# OwlRack.net
KiCad netlist of a schematic drawn in EAGLE
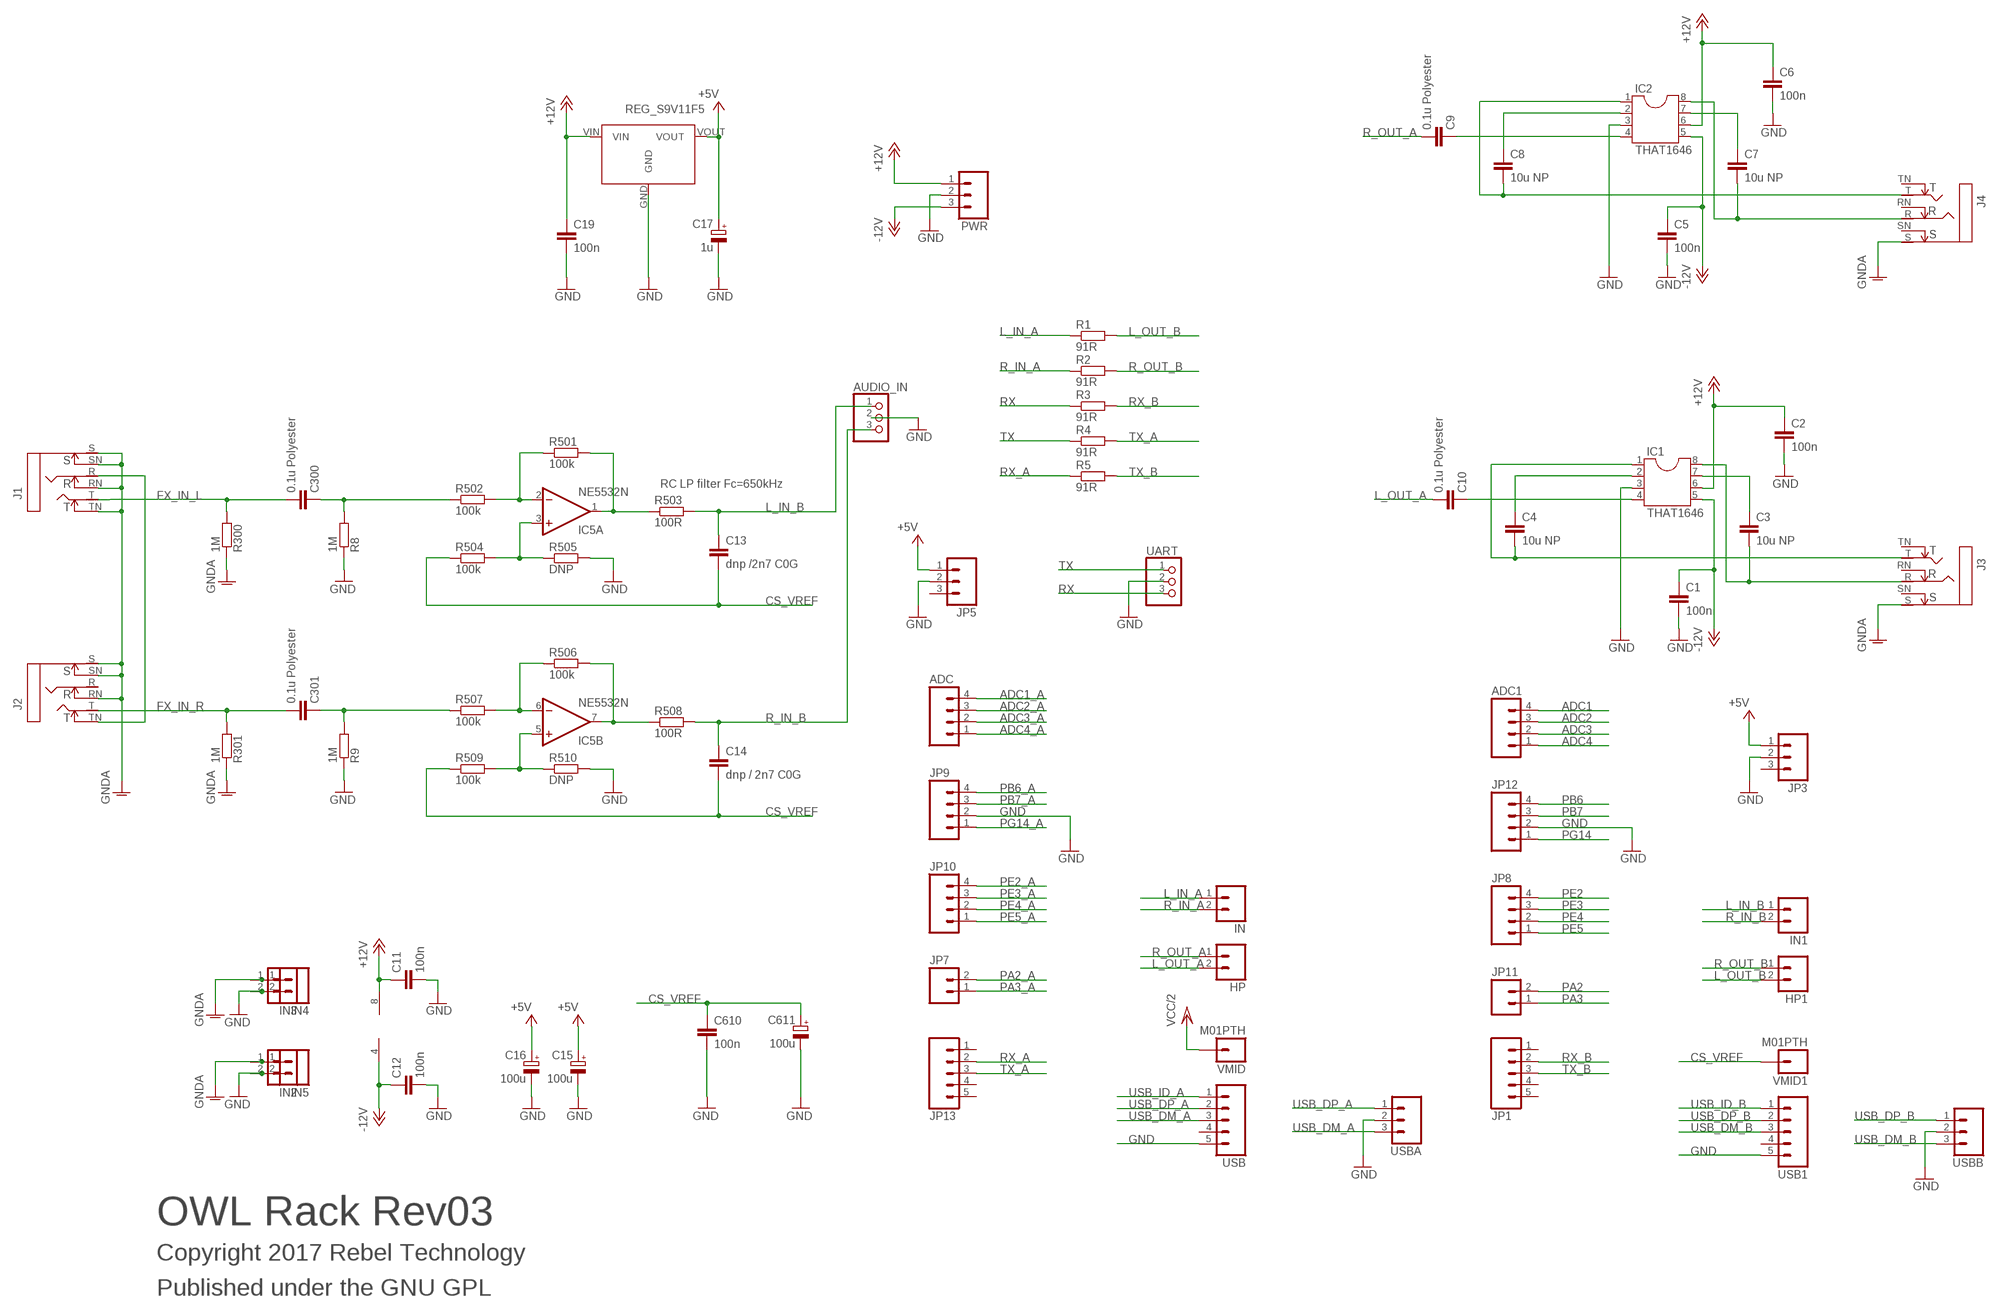
[diagram p0: schematic, sheet 1]

(export (version "E")
  (design (tool "Eeschema 10.0.6"))
  (components
    (comp (ref "ADC")
      (value "M04PTH")
      (footprint "eagle-import:1X04")
      (libsource (lib "eagle-import") (part "M04PTH"))
    )
    (comp (ref "ADC1")
      (value "M04PTH")
      (footprint "eagle-import:1X04")
      (libsource (lib "eagle-import") (part "M04PTH"))
    )
    (comp (ref "AUDIO_IN")
      (value "CON-JST-1X03PH-TH")
      (footprint "eagle-import:JST-B3B-PH-KL")
      (libsource (lib "eagle-import") (part "CON-JST-1X03PH-TH"))
    )
    (comp (ref "C1")
      (value "100n")
      (footprint "eagle-import:C050-025X075")
      (libsource (lib "eagle-import") (part "C-EU050-025X075"))
    )
    (comp (ref "C2")
      (value "100n")
      (footprint "eagle-import:C050-025X075")
      (libsource (lib "eagle-import") (part "C-EU050-025X075"))
    )
    (comp (ref "C3")
      (value "10u NP")
      (footprint "eagle-import:C050-025X075")
      (libsource (lib "eagle-import") (part "C-EU050-025X075"))
    )
    (comp (ref "C4")
      (value "10u NP")
      (footprint "eagle-import:C050-025X075")
      (libsource (lib "eagle-import") (part "C-EU050-025X075"))
    )
    (comp (ref "C5")
      (value "100n")
      (footprint "eagle-import:C050-025X075")
      (libsource (lib "eagle-import") (part "C-EU050-025X075"))
    )
    (comp (ref "C6")
      (value "100n")
      (footprint "eagle-import:C050-025X075")
      (libsource (lib "eagle-import") (part "C-EU050-025X075"))
    )
    (comp (ref "C7")
      (value "10u NP")
      (footprint "eagle-import:C050-025X075")
      (libsource (lib "eagle-import") (part "C-EU050-025X075"))
    )
    (comp (ref "C8")
      (value "10u NP")
      (footprint "eagle-import:C050-025X075")
      (libsource (lib "eagle-import") (part "C-EU050-025X075"))
    )
    (comp (ref "C9")
      (value "0.1u Polyester")
      (footprint "eagle-import:C5B3.5")
      (libsource (lib "eagle-import") (part "C5/3.5"))
    )
    (comp (ref "C10")
      (value "0.1u Polyester")
      (footprint "eagle-import:C5B3.5")
      (libsource (lib "eagle-import") (part "C5/3.5"))
    )
    (comp (ref "C11")
      (value "100n")
      (footprint "eagle-import:C050-025X075")
      (libsource (lib "eagle-import") (part "C-EU050-025X075"))
    )
    (comp (ref "C12")
      (value "100n")
      (footprint "eagle-import:C050-025X075")
      (libsource (lib "eagle-import") (part "C-EU050-025X075"))
    )
    (comp (ref "C13")
      (value "dnp /2n7 C0G")
      (footprint "eagle-import:C050-025X075")
      (libsource (lib "eagle-import") (part "C-EU050-025X075"))
    )
    (comp (ref "C14")
      (value "dnp / 2n7 C0G")
      (footprint "eagle-import:C050-025X075")
      (libsource (lib "eagle-import") (part "C-EU050-025X075"))
    )
    (comp (ref "C15")
      (value "100u")
      (footprint "eagle-import:E2,5-7")
      (libsource (lib "eagle-import") (part "CPOL-EUE2.5-7"))
    )
    (comp (ref "C16")
      (value "100u")
      (footprint "eagle-import:E2,5-7")
      (libsource (lib "eagle-import") (part "CPOL-EUE2.5-7"))
    )
    (comp (ref "C17")
      (value "1u")
      (footprint "eagle-import:E2,5-7")
      (libsource (lib "eagle-import") (part "CPOL-EUE2.5-7"))
    )
    (comp (ref "C19")
      (value "100n")
      (footprint "eagle-import:C050-025X075")
      (libsource (lib "eagle-import") (part "C-EU050-025X075"))
    )
    (comp (ref "C300")
      (value "0.1u Polyester")
      (footprint "eagle-import:C5B3.5")
      (libsource (lib "eagle-import") (part "C5/3.5"))
    )
    (comp (ref "C301")
      (value "0.1u Polyester")
      (footprint "eagle-import:C5B3.5")
      (libsource (lib "eagle-import") (part "C5/3.5"))
    )
    (comp (ref "C610")
      (value "100n")
      (footprint "eagle-import:C050-025X075")
      (libsource (lib "eagle-import") (part "C-EU050-025X075"))
    )
    (comp (ref "C611")
      (value "100u")
      (footprint "eagle-import:E2,5-7")
      (libsource (lib "eagle-import") (part "CPOL-EUE2.5-7"))
    )
    (comp (ref "HP")
      (value "M02PTH")
      (footprint "eagle-import:1X02")
      (libsource (lib "eagle-import") (part "M02PTH"))
    )
    (comp (ref "HP1")
      (value "M02PTH")
      (footprint "eagle-import:1X02")
      (libsource (lib "eagle-import") (part "M02PTH"))
    )
    (comp (ref "IC1")
      (value "THAT1646")
      (footprint "eagle-import:DIL08")
      (libsource (lib "eagle-import") (part "DIL8"))
    )
    (comp (ref "IC2")
      (value "THAT1646")
      (footprint "eagle-import:DIL08")
      (libsource (lib "eagle-import") (part "DIL8"))
    )
    (comp (ref "IC3")
      (value "REG_S9V11F5")
      (footprint "eagle-import:REG_S9V11F5")
      (libsource (lib "eagle-import") (part "REG_S9V11F5"))
    )
    (comp (ref "IC5")
      (value "NE5532N")
      (footprint "eagle-import:DIL08")
      (libsource (lib "eagle-import") (part "NE5532N"))
    )
    (comp (ref "IN")
      (value "M02PTH")
      (footprint "eagle-import:1X02")
      (libsource (lib "eagle-import") (part "M02PTH"))
    )
    (comp (ref "IN1")
      (value "M02PTH")
      (footprint "eagle-import:1X02")
      (libsource (lib "eagle-import") (part "M02PTH"))
    )
    (comp (ref "IN2")
      (value "M02PTH")
      (footprint "eagle-import:1X02")
      (libsource (lib "eagle-import") (part "M02PTH"))
    )
    (comp (ref "IN3")
      (value "M02PTH")
      (footprint "eagle-import:1X02")
      (libsource (lib "eagle-import") (part "M02PTH"))
    )
    (comp (ref "IN4")
      (value "M02PTH")
      (footprint "eagle-import:1X02")
      (libsource (lib "eagle-import") (part "M02PTH"))
    )
    (comp (ref "IN5")
      (value "M02PTH")
      (footprint "eagle-import:1X02")
      (libsource (lib "eagle-import") (part "M02PTH"))
    )
    (comp (ref "J1")
      (value "NEUTRIK_NRJ6HFSTD")
      (footprint "eagle-import:NRJ6HF")
      (libsource (lib "eagle-import") (part "NEUTRIK_NRJ6HFSTD"))
    )
    (comp (ref "J2")
      (value "NEUTRIK_NRJ6HFSTD")
      (footprint "eagle-import:NRJ6HF")
      (libsource (lib "eagle-import") (part "NEUTRIK_NRJ6HFSTD"))
    )
    (comp (ref "J3")
      (value "NEUTRIK_NRJ6HFSTD")
      (footprint "eagle-import:NRJ6HF")
      (libsource (lib "eagle-import") (part "NEUTRIK_NRJ6HFSTD"))
    )
    (comp (ref "J4")
      (value "NEUTRIK_NRJ6HFSTD")
      (footprint "eagle-import:NRJ6HF")
      (libsource (lib "eagle-import") (part "NEUTRIK_NRJ6HFSTD"))
    )
    (comp (ref "JP1")
      (value "M05PTH")
      (footprint "eagle-import:1X05")
      (libsource (lib "eagle-import") (part "M05PTH"))
    )
    (comp (ref "JP3")
      (value "M03PTH")
      (footprint "eagle-import:1X03")
      (libsource (lib "eagle-import") (part "M03PTH"))
    )
    (comp (ref "JP5")
      (value "M03PTH")
      (footprint "eagle-import:1X03")
      (libsource (lib "eagle-import") (part "M03PTH"))
    )
    (comp (ref "JP7")
      (value "M02PTH")
      (footprint "eagle-import:1X02")
      (libsource (lib "eagle-import") (part "M02PTH"))
    )
    (comp (ref "JP8")
      (value "M04PTH")
      (footprint "eagle-import:1X04")
      (libsource (lib "eagle-import") (part "M04PTH"))
    )
    (comp (ref "JP9")
      (value "M04PTH")
      (footprint "eagle-import:1X04")
      (libsource (lib "eagle-import") (part "M04PTH"))
    )
    (comp (ref "JP10")
      (value "M04PTH")
      (footprint "eagle-import:1X04")
      (libsource (lib "eagle-import") (part "M04PTH"))
    )
    (comp (ref "JP11")
      (value "M02PTH")
      (footprint "eagle-import:1X02")
      (libsource (lib "eagle-import") (part "M02PTH"))
    )
    (comp (ref "JP12")
      (value "M04PTH")
      (footprint "eagle-import:1X04")
      (libsource (lib "eagle-import") (part "M04PTH"))
    )
    (comp (ref "JP13")
      (value "M05PTH")
      (footprint "eagle-import:1X05")
      (libsource (lib "eagle-import") (part "M05PTH"))
    )
    (comp (ref "PWR")
      (value "M03PTH")
      (footprint "eagle-import:1X03")
      (libsource (lib "eagle-import") (part "M03PTH"))
    )
    (comp (ref "R1")
      (value "91R")
      (footprint "eagle-import:0204_7")
      (libsource (lib "eagle-import") (part "R-EU_0204/7"))
    )
    (comp (ref "R2")
      (value "91R")
      (footprint "eagle-import:0204_7")
      (libsource (lib "eagle-import") (part "R-EU_0204/7"))
    )
    (comp (ref "R3")
      (value "91R")
      (footprint "eagle-import:0204_7")
      (libsource (lib "eagle-import") (part "R-EU_0204/7"))
    )
    (comp (ref "R4")
      (value "91R")
      (footprint "eagle-import:0204_7")
      (libsource (lib "eagle-import") (part "R-EU_0204/7"))
    )
    (comp (ref "R5")
      (value "91R")
      (footprint "eagle-import:0204_7")
      (libsource (lib "eagle-import") (part "R-EU_0204/7"))
    )
    (comp (ref "R8")
      (value "1M")
      (footprint "eagle-import:0204_7")
      (libsource (lib "eagle-import") (part "R-EU_0204/7"))
    )
    (comp (ref "R9")
      (value "1M")
      (footprint "eagle-import:0204_7")
      (libsource (lib "eagle-import") (part "R-EU_0204/7"))
    )
    (comp (ref "R300")
      (value "1M")
      (footprint "eagle-import:0204_7")
      (libsource (lib "eagle-import") (part "R-EU_0204/7"))
    )
    (comp (ref "R301")
      (value "1M")
      (footprint "eagle-import:0204_7")
      (libsource (lib "eagle-import") (part "R-EU_0204/7"))
    )
    (comp (ref "R501")
      (value "100k")
      (footprint "eagle-import:0204_7")
      (libsource (lib "eagle-import") (part "R-EU_0204/7"))
    )
    (comp (ref "R502")
      (value "100k")
      (footprint "eagle-import:0204_7")
      (libsource (lib "eagle-import") (part "R-EU_0204/7"))
    )
    (comp (ref "R503")
      (value "100R")
      (footprint "eagle-import:0204_7")
      (libsource (lib "eagle-import") (part "R-EU_0204/7"))
    )
    (comp (ref "R504")
      (value "100k")
      (footprint "eagle-import:0204_7")
      (libsource (lib "eagle-import") (part "R-EU_0204/7"))
    )
    (comp (ref "R505")
      (value "DNP")
      (footprint "eagle-import:0204_7")
      (libsource (lib "eagle-import") (part "R-EU_0204/7"))
    )
    (comp (ref "R506")
      (value "100k")
      (footprint "eagle-import:0204_7")
      (libsource (lib "eagle-import") (part "R-EU_0204/7"))
    )
    (comp (ref "R507")
      (value "100k")
      (footprint "eagle-import:0204_7")
      (libsource (lib "eagle-import") (part "R-EU_0204/7"))
    )
    (comp (ref "R508")
      (value "100R")
      (footprint "eagle-import:0204_7")
      (libsource (lib "eagle-import") (part "R-EU_0204/7"))
    )
    (comp (ref "R509")
      (value "100k")
      (footprint "eagle-import:0204_7")
      (libsource (lib "eagle-import") (part "R-EU_0204/7"))
    )
    (comp (ref "R510")
      (value "DNP")
      (footprint "eagle-import:0204_7")
      (libsource (lib "eagle-import") (part "R-EU_0204/7"))
    )
    (comp (ref "UART")
      (value "CON-JST-1X03PH-TH")
      (footprint "eagle-import:JST-B3B-PH-KL")
      (libsource (lib "eagle-import") (part "CON-JST-1X03PH-TH"))
    )
    (comp (ref "USB")
      (value "M05PTH")
      (footprint "eagle-import:1X05")
      (libsource (lib "eagle-import") (part "M05PTH"))
    )
    (comp (ref "USB1")
      (value "M05PTH")
      (footprint "eagle-import:1X05")
      (libsource (lib "eagle-import") (part "M05PTH"))
    )
    (comp (ref "USBA")
      (value "M03PTH")
      (footprint "eagle-import:1X03")
      (libsource (lib "eagle-import") (part "M03PTH"))
    )
    (comp (ref "USBB")
      (value "M03PTH")
      (footprint "eagle-import:1X03")
      (libsource (lib "eagle-import") (part "M03PTH"))
    )
    (comp (ref "VMID")
      (value "M01PTH")
      (footprint "eagle-import:1X01")
      (libsource (lib "eagle-import") (part "M01PTH"))
    )
    (comp (ref "VMID1")
      (value "M01PTH")
      (footprint "eagle-import:1X01")
      (libsource (lib "eagle-import") (part "M01PTH"))
    )
  )
  (nets
    (net (code "1") (name "+5V") (class "Default")
      (node (ref "C15") (pin "+") (pinfunction "+_+") (pintype "passive"))
      (node (ref "C16") (pin "+") (pinfunction "+_+") (pintype "passive"))
      (node (ref "C17") (pin "+") (pinfunction "+_+") (pintype "passive"))
      (node (ref "IC3") (pin "VOUT") (pinfunction "VOUT_VOUT") (pintype "output"))
      (node (ref "JP3") (pin "1") (pinfunction "1_1") (pintype "passive"))
      (node (ref "JP5") (pin "1") (pinfunction "1_1") (pintype "passive"))
    )
    (net (code "2") (name "+12V") (class "Default")
      (node (ref "C11") (pin "1") (pinfunction "1_1") (pintype "passive"))
      (node (ref "C19") (pin "1") (pinfunction "1_1") (pintype "passive"))
      (node (ref "C2") (pin "1") (pinfunction "1_1") (pintype "passive"))
      (node (ref "C6") (pin "1") (pinfunction "1_1") (pintype "passive"))
      (node (ref "IC1") (pin "6") (pinfunction "6_6") (pintype "passive"))
      (node (ref "IC2") (pin "6") (pinfunction "6_6") (pintype "passive"))
      (node (ref "IC3") (pin "VIN") (pinfunction "VIN_VIN") (pintype "input"))
      (node (ref "IC5") (pin "8") (pinfunction "V+_8") (pintype "power_in"))
      (node (ref "PWR") (pin "1") (pinfunction "1_1") (pintype "passive"))
    )
    (net (code "3") (name "-12V") (class "Default")
      (node (ref "C1") (pin "1") (pinfunction "1_1") (pintype "passive"))
      (node (ref "C12") (pin "1") (pinfunction "1_1") (pintype "passive"))
      (node (ref "C5") (pin "1") (pinfunction "1_1") (pintype "passive"))
      (node (ref "IC1") (pin "5") (pinfunction "5_5") (pintype "passive"))
      (node (ref "IC2") (pin "5") (pinfunction "5_5") (pintype "passive"))
      (node (ref "IC5") (pin "4") (pinfunction "V-_4") (pintype "power_in"))
      (node (ref "PWR") (pin "3") (pinfunction "3_3") (pintype "passive"))
    )
    (net (code "4") (name "/ADC1") (class "Default")
      (node (ref "ADC1") (pin "4") (pinfunction "4_4") (pintype "passive"))
    )
    (net (code "5") (name "/ADC1_A") (class "Default")
      (node (ref "ADC") (pin "4") (pinfunction "4_4") (pintype "passive"))
    )
    (net (code "6") (name "/ADC2") (class "Default")
      (node (ref "ADC1") (pin "3") (pinfunction "3_3") (pintype "passive"))
    )
    (net (code "7") (name "/ADC2_A") (class "Default")
      (node (ref "ADC") (pin "3") (pinfunction "3_3") (pintype "passive"))
    )
    (net (code "8") (name "/ADC3") (class "Default")
      (node (ref "ADC1") (pin "2") (pinfunction "2_2") (pintype "passive"))
    )
    (net (code "9") (name "/ADC3_A") (class "Default")
      (node (ref "ADC") (pin "2") (pinfunction "2_2") (pintype "passive"))
    )
    (net (code "10") (name "/ADC4") (class "Default")
      (node (ref "ADC1") (pin "1") (pinfunction "1_1") (pintype "passive"))
    )
    (net (code "11") (name "/ADC4_A") (class "Default")
      (node (ref "ADC") (pin "1") (pinfunction "1_1") (pintype "passive"))
    )
    (net (code "12") (name "/CS_VREF") (class "Default")
      (node (ref "C13") (pin "2") (pinfunction "2_2") (pintype "passive"))
      (node (ref "C14") (pin "2") (pinfunction "2_2") (pintype "passive"))
      (node (ref "C610") (pin "1") (pinfunction "1_1") (pintype "passive"))
      (node (ref "C611") (pin "+") (pinfunction "+_+") (pintype "passive"))
      (node (ref "R504") (pin "1") (pinfunction "1_1") (pintype "passive"))
      (node (ref "R509") (pin "1") (pinfunction "1_1") (pintype "passive"))
      (node (ref "VMID1") (pin "1") (pinfunction "1_1") (pintype "passive"))
    )
    (net (code "13") (name "/FX_IN_L") (class "Default")
      (node (ref "C300") (pin "2") (pinfunction "2_2") (pintype "passive"))
      (node (ref "J1") (pin "T") (pinfunction "T_T") (pintype "passive"))
      (node (ref "R300") (pin "2") (pinfunction "2_2") (pintype "passive"))
    )
    (net (code "14") (name "/FX_IN_R") (class "Default")
      (node (ref "C301") (pin "2") (pinfunction "2_2") (pintype "passive"))
      (node (ref "J2") (pin "T") (pinfunction "T_T") (pintype "passive"))
      (node (ref "R301") (pin "2") (pinfunction "2_2") (pintype "passive"))
    )
    (net (code "15") (name "/L_IN_A") (class "Default")
      (node (ref "IN") (pin "1") (pinfunction "1_1") (pintype "passive"))
      (node (ref "R1") (pin "1") (pinfunction "1_1") (pintype "passive"))
    )
    (net (code "16") (name "/L_IN_B") (class "Default")
      (node (ref "AUDIO_IN") (pin "1") (pinfunction "1_1") (pintype "passive"))
      (node (ref "C13") (pin "1") (pinfunction "1_1") (pintype "passive"))
      (node (ref "IN1") (pin "1") (pinfunction "1_1") (pintype "passive"))
      (node (ref "R503") (pin "2") (pinfunction "2_2") (pintype "passive"))
    )
    (net (code "17") (name "/L_OUT_A") (class "Default")
      (node (ref "C10") (pin "2") (pinfunction "2_2") (pintype "passive"))
      (node (ref "HP") (pin "2") (pinfunction "2_2") (pintype "passive"))
    )
    (net (code "18") (name "/L_OUT_B") (class "Default")
      (node (ref "HP1") (pin "2") (pinfunction "2_2") (pintype "passive"))
      (node (ref "R1") (pin "2") (pinfunction "2_2") (pintype "passive"))
    )
    (net (code "19") (name "/PA2") (class "Default")
      (node (ref "JP11") (pin "2") (pinfunction "2_2") (pintype "passive"))
    )
    (net (code "20") (name "/PA2_A") (class "Default")
      (node (ref "JP7") (pin "2") (pinfunction "2_2") (pintype "passive"))
    )
    (net (code "21") (name "/PA3") (class "Default")
      (node (ref "JP11") (pin "1") (pinfunction "1_1") (pintype "passive"))
    )
    (net (code "22") (name "/PA3_A") (class "Default")
      (node (ref "JP7") (pin "1") (pinfunction "1_1") (pintype "passive"))
    )
    (net (code "23") (name "/PB6") (class "Default")
      (node (ref "JP12") (pin "4") (pinfunction "4_4") (pintype "passive"))
    )
    (net (code "24") (name "/PB6_A") (class "Default")
      (node (ref "JP9") (pin "4") (pinfunction "4_4") (pintype "passive"))
    )
    (net (code "25") (name "/PB7") (class "Default")
      (node (ref "JP12") (pin "3") (pinfunction "3_3") (pintype "passive"))
    )
    (net (code "26") (name "/PB7_A") (class "Default")
      (node (ref "JP9") (pin "3") (pinfunction "3_3") (pintype "passive"))
    )
    (net (code "27") (name "/PE2") (class "Default")
      (node (ref "JP8") (pin "4") (pinfunction "4_4") (pintype "passive"))
    )
    (net (code "28") (name "/PE2_A") (class "Default")
      (node (ref "JP10") (pin "4") (pinfunction "4_4") (pintype "passive"))
    )
    (net (code "29") (name "/PE3") (class "Default")
      (node (ref "JP8") (pin "3") (pinfunction "3_3") (pintype "passive"))
    )
    (net (code "30") (name "/PE3_A") (class "Default")
      (node (ref "JP10") (pin "3") (pinfunction "3_3") (pintype "passive"))
    )
    (net (code "31") (name "/PE4") (class "Default")
      (node (ref "JP8") (pin "2") (pinfunction "2_2") (pintype "passive"))
    )
    (net (code "32") (name "/PE4_A") (class "Default")
      (node (ref "JP10") (pin "2") (pinfunction "2_2") (pintype "passive"))
    )
    (net (code "33") (name "/PE5") (class "Default")
      (node (ref "JP8") (pin "1") (pinfunction "1_1") (pintype "passive"))
    )
    (net (code "34") (name "/PE5_A") (class "Default")
      (node (ref "JP10") (pin "1") (pinfunction "1_1") (pintype "passive"))
    )
    (net (code "35") (name "/PG14") (class "Default")
      (node (ref "JP12") (pin "1") (pinfunction "1_1") (pintype "passive"))
    )
    (net (code "36") (name "/PG14_A") (class "Default")
      (node (ref "JP9") (pin "1") (pinfunction "1_1") (pintype "passive"))
    )
    (net (code "37") (name "/RX") (class "Default")
      (node (ref "R3") (pin "1") (pinfunction "1_1") (pintype "passive"))
      (node (ref "UART") (pin "3") (pinfunction "3_3") (pintype "passive"))
    )
    (net (code "38") (name "/RX_A") (class "Default")
      (node (ref "JP13") (pin "2") (pinfunction "2_2") (pintype "passive"))
      (node (ref "R5") (pin "1") (pinfunction "1_1") (pintype "passive"))
    )
    (net (code "39") (name "/RX_B") (class "Default")
      (node (ref "JP1") (pin "2") (pinfunction "2_2") (pintype "passive"))
      (node (ref "R3") (pin "2") (pinfunction "2_2") (pintype "passive"))
    )
    (net (code "40") (name "/R_IN_A") (class "Default")
      (node (ref "IN") (pin "2") (pinfunction "2_2") (pintype "passive"))
      (node (ref "R2") (pin "1") (pinfunction "1_1") (pintype "passive"))
    )
    (net (code "41") (name "/R_IN_B") (class "Default")
      (node (ref "AUDIO_IN") (pin "3") (pinfunction "3_3") (pintype "passive"))
      (node (ref "C14") (pin "1") (pinfunction "1_1") (pintype "passive"))
      (node (ref "IN1") (pin "2") (pinfunction "2_2") (pintype "passive"))
      (node (ref "R508") (pin "2") (pinfunction "2_2") (pintype "passive"))
    )
    (net (code "42") (name "/R_OUT_A") (class "Default")
      (node (ref "C9") (pin "2") (pinfunction "2_2") (pintype "passive"))
      (node (ref "HP") (pin "1") (pinfunction "1_1") (pintype "passive"))
    )
    (net (code "43") (name "/R_OUT_B") (class "Default")
      (node (ref "HP1") (pin "1") (pinfunction "1_1") (pintype "passive"))
      (node (ref "R2") (pin "2") (pinfunction "2_2") (pintype "passive"))
    )
    (net (code "44") (name "/TX") (class "Default")
      (node (ref "R4") (pin "1") (pinfunction "1_1") (pintype "passive"))
      (node (ref "UART") (pin "1") (pinfunction "1_1") (pintype "passive"))
    )
    (net (code "45") (name "/TX_A") (class "Default")
      (node (ref "JP13") (pin "3") (pinfunction "3_3") (pintype "passive"))
      (node (ref "R4") (pin "2") (pinfunction "2_2") (pintype "passive"))
    )
    (net (code "46") (name "/TX_B") (class "Default")
      (node (ref "JP1") (pin "3") (pinfunction "3_3") (pintype "passive"))
      (node (ref "R5") (pin "2") (pinfunction "2_2") (pintype "passive"))
    )
    (net (code "47") (name "/USB_DM_A") (class "Default")
      (node (ref "USB") (pin "3") (pinfunction "3_3") (pintype "passive"))
      (node (ref "USBA") (pin "3") (pinfunction "3_3") (pintype "passive"))
    )
    (net (code "48") (name "/USB_DM_B") (class "Default")
      (node (ref "USB1") (pin "3") (pinfunction "3_3") (pintype "passive"))
      (node (ref "USBB") (pin "3") (pinfunction "3_3") (pintype "passive"))
    )
    (net (code "49") (name "/USB_DP_A") (class "Default")
      (node (ref "USB") (pin "2") (pinfunction "2_2") (pintype "passive"))
      (node (ref "USBA") (pin "1") (pinfunction "1_1") (pintype "passive"))
    )
    (net (code "50") (name "/USB_DP_B") (class "Default")
      (node (ref "USB1") (pin "2") (pinfunction "2_2") (pintype "passive"))
      (node (ref "USBB") (pin "1") (pinfunction "1_1") (pintype "passive"))
    )
    (net (code "51") (name "/USB_ID_A") (class "Default")
      (node (ref "USB") (pin "1") (pinfunction "1_1") (pintype "passive"))
    )
    (net (code "52") (name "/USB_ID_B") (class "Default")
      (node (ref "USB1") (pin "1") (pinfunction "1_1") (pintype "passive"))
    )
    (net (code "53") (name "GND") (class "Default")
      (node (ref "AUDIO_IN") (pin "2") (pinfunction "2_2") (pintype "passive"))
      (node (ref "C1") (pin "2") (pinfunction "2_2") (pintype "passive"))
      (node (ref "C11") (pin "2") (pinfunction "2_2") (pintype "passive"))
      (node (ref "C12") (pin "2") (pinfunction "2_2") (pintype "passive"))
      (node (ref "C15") (pin "-") (pinfunction "-_-") (pintype "passive"))
      (node (ref "C16") (pin "-") (pinfunction "-_-") (pintype "passive"))
      (node (ref "C17") (pin "-") (pinfunction "-_-") (pintype "passive"))
      (node (ref "C19") (pin "2") (pinfunction "2_2") (pintype "passive"))
      (node (ref "C2") (pin "2") (pinfunction "2_2") (pintype "passive"))
      (node (ref "C5") (pin "2") (pinfunction "2_2") (pintype "passive"))
      (node (ref "C6") (pin "2") (pinfunction "2_2") (pintype "passive"))
      (node (ref "C610") (pin "2") (pinfunction "2_2") (pintype "passive"))
      (node (ref "C611") (pin "-") (pinfunction "-_-") (pintype "passive"))
      (node (ref "IC1") (pin "3") (pinfunction "3_3") (pintype "passive"))
      (node (ref "IC2") (pin "3") (pinfunction "3_3") (pintype "passive"))
      (node (ref "IC3") (pin "GND") (pinfunction "GND_GND") (pintype "power_in"))
      (node (ref "IN2") (pin "2") (pinfunction "2_2") (pintype "passive"))
      (node (ref "IN3") (pin "2") (pinfunction "2_2") (pintype "passive"))
      (node (ref "IN4") (pin "2") (pinfunction "2_2") (pintype "passive"))
      (node (ref "IN5") (pin "2") (pinfunction "2_2") (pintype "passive"))
      (node (ref "JP12") (pin "2") (pinfunction "2_2") (pintype "passive"))
      (node (ref "JP3") (pin "2") (pinfunction "2_2") (pintype "passive"))
      (node (ref "JP5") (pin "2") (pinfunction "2_2") (pintype "passive"))
      (node (ref "JP9") (pin "2") (pinfunction "2_2") (pintype "passive"))
      (node (ref "PWR") (pin "2") (pinfunction "2_2") (pintype "passive"))
      (node (ref "R505") (pin "2") (pinfunction "2_2") (pintype "passive"))
      (node (ref "R510") (pin "2") (pinfunction "2_2") (pintype "passive"))
      (node (ref "R8") (pin "1") (pinfunction "1_1") (pintype "passive"))
      (node (ref "R9") (pin "1") (pinfunction "1_1") (pintype "passive"))
      (node (ref "UART") (pin "2") (pinfunction "2_2") (pintype "passive"))
      (node (ref "USB") (pin "5") (pinfunction "5_5") (pintype "passive"))
      (node (ref "USB1") (pin "5") (pinfunction "5_5") (pintype "passive"))
      (node (ref "USBA") (pin "2") (pinfunction "2_2") (pintype "passive"))
      (node (ref "USBB") (pin "2") (pinfunction "2_2") (pintype "passive"))
    )
    (net (code "54") (name "GNDA") (class "Default")
      (node (ref "IN2") (pin "1") (pinfunction "1_1") (pintype "passive"))
      (node (ref "IN3") (pin "1") (pinfunction "1_1") (pintype "passive"))
      (node (ref "IN4") (pin "1") (pinfunction "1_1") (pintype "passive"))
      (node (ref "IN5") (pin "1") (pinfunction "1_1") (pintype "passive"))
      (node (ref "J1") (pin "RN") (pinfunction "RN_RN") (pintype "passive"))
      (node (ref "J1") (pin "S") (pinfunction "S_S") (pintype "passive"))
      (node (ref "J1") (pin "SN") (pinfunction "SN_SN") (pintype "passive"))
      (node (ref "J1") (pin "TN") (pinfunction "TN_TN") (pintype "passive"))
      (node (ref "J2") (pin "RN") (pinfunction "RN_RN") (pintype "passive"))
      (node (ref "J2") (pin "S") (pinfunction "S_S") (pintype "passive"))
      (node (ref "J2") (pin "SN") (pinfunction "SN_SN") (pintype "passive"))
      (node (ref "J3") (pin "S") (pinfunction "S_S") (pintype "passive"))
      (node (ref "J4") (pin "S") (pinfunction "S_S") (pintype "passive"))
      (node (ref "R300") (pin "1") (pinfunction "1_1") (pintype "passive"))
      (node (ref "R301") (pin "1") (pinfunction "1_1") (pintype "passive"))
    )
    (net (code "55") (name "Net-(C3-Pad1)") (class "Default")
      (node (ref "C3") (pin "1") (pinfunction "1_1") (pintype "passive"))
      (node (ref "IC1") (pin "7") (pinfunction "7_7") (pintype "passive"))
    )
    (net (code "56") (name "Net-(C3-Pad2)") (class "Default")
      (node (ref "C3") (pin "2") (pinfunction "2_2") (pintype "passive"))
      (node (ref "IC1") (pin "8") (pinfunction "8_8") (pintype "passive"))
      (node (ref "J3") (pin "R") (pinfunction "R_R") (pintype "passive"))
    )
    (net (code "57") (name "Net-(C4-Pad1)") (class "Default")
      (node (ref "C4") (pin "1") (pinfunction "1_1") (pintype "passive"))
      (node (ref "IC1") (pin "2") (pinfunction "2_2") (pintype "passive"))
    )
    (net (code "58") (name "Net-(C4-Pad2)") (class "Default")
      (node (ref "C4") (pin "2") (pinfunction "2_2") (pintype "passive"))
      (node (ref "IC1") (pin "1") (pinfunction "1_1") (pintype "passive"))
      (node (ref "J3") (pin "T") (pinfunction "T_T") (pintype "passive"))
    )
    (net (code "59") (name "Net-(C7-Pad1)") (class "Default")
      (node (ref "C7") (pin "1") (pinfunction "1_1") (pintype "passive"))
      (node (ref "IC2") (pin "7") (pinfunction "7_7") (pintype "passive"))
    )
    (net (code "60") (name "Net-(C7-Pad2)") (class "Default")
      (node (ref "C7") (pin "2") (pinfunction "2_2") (pintype "passive"))
      (node (ref "IC2") (pin "8") (pinfunction "8_8") (pintype "passive"))
      (node (ref "J4") (pin "R") (pinfunction "R_R") (pintype "passive"))
    )
    (net (code "61") (name "Net-(C8-Pad1)") (class "Default")
      (node (ref "C8") (pin "1") (pinfunction "1_1") (pintype "passive"))
      (node (ref "IC2") (pin "2") (pinfunction "2_2") (pintype "passive"))
    )
    (net (code "62") (name "Net-(C8-Pad2)") (class "Default")
      (node (ref "C8") (pin "2") (pinfunction "2_2") (pintype "passive"))
      (node (ref "IC2") (pin "1") (pinfunction "1_1") (pintype "passive"))
      (node (ref "J4") (pin "T") (pinfunction "T_T") (pintype "passive"))
    )
    (net (code "63") (name "Net-(C9-Pad1)") (class "Default")
      (node (ref "C9") (pin "1") (pinfunction "1_1") (pintype "passive"))
      (node (ref "IC2") (pin "4") (pinfunction "4_4") (pintype "passive"))
    )
    (net (code "64") (name "Net-(C10-Pad1)") (class "Default")
      (node (ref "C10") (pin "1") (pinfunction "1_1") (pintype "passive"))
      (node (ref "IC1") (pin "4") (pinfunction "4_4") (pintype "passive"))
    )
    (net (code "65") (name "Net-(C300-Pad1)") (class "Default")
      (node (ref "C300") (pin "1") (pinfunction "1_1") (pintype "passive"))
      (node (ref "R502") (pin "1") (pinfunction "1_1") (pintype "passive"))
      (node (ref "R8") (pin "2") (pinfunction "2_2") (pintype "passive"))
    )
    (net (code "66") (name "Net-(C301-Pad1)") (class "Default")
      (node (ref "C301") (pin "1") (pinfunction "1_1") (pintype "passive"))
      (node (ref "R507") (pin "1") (pinfunction "1_1") (pintype "passive"))
      (node (ref "R9") (pin "2") (pinfunction "2_2") (pintype "passive"))
    )
    (net (code "67") (name "Net-(IC5A-+IN)") (class "Default")
      (node (ref "IC5") (pin "3") (pinfunction "+IN_3") (pintype "input"))
      (node (ref "R504") (pin "2") (pinfunction "2_2") (pintype "passive"))
      (node (ref "R505") (pin "1") (pinfunction "1_1") (pintype "passive"))
    )
    (net (code "68") (name "Net-(IC5A--IN)") (class "Default")
      (node (ref "IC5") (pin "2") (pinfunction "-IN_2") (pintype "input"))
      (node (ref "R501") (pin "1") (pinfunction "1_1") (pintype "passive"))
      (node (ref "R502") (pin "2") (pinfunction "2_2") (pintype "passive"))
    )
    (net (code "69") (name "Net-(IC5A-OUT)") (class "Default")
      (node (ref "IC5") (pin "1") (pinfunction "OUT_1") (pintype "output"))
      (node (ref "R501") (pin "2") (pinfunction "2_2") (pintype "passive"))
      (node (ref "R503") (pin "1") (pinfunction "1_1") (pintype "passive"))
    )
    (net (code "70") (name "Net-(IC5B-+IN)") (class "Default")
      (node (ref "IC5") (pin "5") (pinfunction "+IN_5") (pintype "input"))
      (node (ref "R509") (pin "2") (pinfunction "2_2") (pintype "passive"))
      (node (ref "R510") (pin "1") (pinfunction "1_1") (pintype "passive"))
    )
    (net (code "71") (name "Net-(IC5B--IN)") (class "Default")
      (node (ref "IC5") (pin "6") (pinfunction "-IN_6") (pintype "input"))
      (node (ref "R506") (pin "1") (pinfunction "1_1") (pintype "passive"))
      (node (ref "R507") (pin "2") (pinfunction "2_2") (pintype "passive"))
    )
    (net (code "72") (name "Net-(IC5B-OUT)") (class "Default")
      (node (ref "IC5") (pin "7") (pinfunction "OUT_7") (pintype "output"))
      (node (ref "R506") (pin "2") (pinfunction "2_2") (pintype "passive"))
      (node (ref "R508") (pin "1") (pinfunction "1_1") (pintype "passive"))
    )
    (net (code "73") (name "Net-(J1-PadR)") (class "Default")
      (node (ref "J1") (pin "R") (pinfunction "R_R") (pintype "passive"))
      (node (ref "J2") (pin "TN") (pinfunction "TN_TN") (pintype "passive"))
    )
    (net (code "74") (name "VCC{slash}2") (class "Default")
      (node (ref "VMID") (pin "1") (pinfunction "1_1") (pintype "passive"))
    )
    (net (code "75") (name "unconnected-(J2-PadR)") (class "Default")
      (node (ref "J2") (pin "R") (pinfunction "R_R") (pintype "passive"))
    )
    (net (code "76") (name "unconnected-(J3-PadRN)") (class "Default")
      (node (ref "J3") (pin "RN") (pinfunction "RN_RN") (pintype "passive"))
    )
    (net (code "77") (name "unconnected-(J3-PadSN)") (class "Default")
      (node (ref "J3") (pin "SN") (pinfunction "SN_SN") (pintype "passive"))
    )
    (net (code "78") (name "unconnected-(J3-PadTN)") (class "Default")
      (node (ref "J3") (pin "TN") (pinfunction "TN_TN") (pintype "passive"))
    )
    (net (code "79") (name "unconnected-(J4-PadRN)") (class "Default")
      (node (ref "J4") (pin "RN") (pinfunction "RN_RN") (pintype "passive"))
    )
    (net (code "80") (name "unconnected-(J4-PadSN)") (class "Default")
      (node (ref "J4") (pin "SN") (pinfunction "SN_SN") (pintype "passive"))
    )
    (net (code "81") (name "unconnected-(J4-PadTN)") (class "Default")
      (node (ref "J4") (pin "TN") (pinfunction "TN_TN") (pintype "passive"))
    )
    (net (code "82") (name "unconnected-(JP1-Pad1)") (class "Default")
      (node (ref "JP1") (pin "1") (pinfunction "1_1") (pintype "passive"))
    )
    (net (code "83") (name "unconnected-(JP1-Pad4)") (class "Default")
      (node (ref "JP1") (pin "4") (pinfunction "4_4") (pintype "passive"))
    )
    (net (code "84") (name "unconnected-(JP1-Pad5)") (class "Default")
      (node (ref "JP1") (pin "5") (pinfunction "5_5") (pintype "passive"))
    )
    (net (code "85") (name "unconnected-(JP3-Pad3)") (class "Default")
      (node (ref "JP3") (pin "3") (pinfunction "3_3") (pintype "passive"))
    )
    (net (code "86") (name "unconnected-(JP5-Pad3)") (class "Default")
      (node (ref "JP5") (pin "3") (pinfunction "3_3") (pintype "passive"))
    )
    (net (code "87") (name "unconnected-(JP13-Pad1)") (class "Default")
      (node (ref "JP13") (pin "1") (pinfunction "1_1") (pintype "passive"))
    )
    (net (code "88") (name "unconnected-(JP13-Pad4)") (class "Default")
      (node (ref "JP13") (pin "4") (pinfunction "4_4") (pintype "passive"))
    )
    (net (code "89") (name "unconnected-(JP13-Pad5)") (class "Default")
      (node (ref "JP13") (pin "5") (pinfunction "5_5") (pintype "passive"))
    )
    (net (code "90") (name "unconnected-(USB-Pad4)") (class "Default")
      (node (ref "USB") (pin "4") (pinfunction "4_4") (pintype "passive"))
    )
    (net (code "91") (name "unconnected-(USB1-Pad4)") (class "Default")
      (node (ref "USB1") (pin "4") (pinfunction "4_4") (pintype "passive"))
    )
  )
)
